# TLM_002_MAX6675.net
KiCad netlist of a schematic drawn in Altium Designer
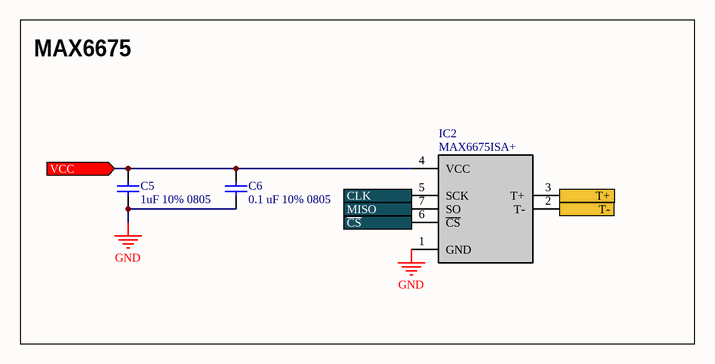
[diagram p0: TLM_002_MAX6675.SchDoc]

(export (version "E")
  (design (tool "Eeschema 10.0.6"))
  (components
    (comp (ref "C5")
      (value "1uF 10% 0805")
      (footprint "CAPC2013X145X50NL20T20")
      (fields (field (name "PART NUMBER") "VJ0805Y105KXQRW1BC") (field (name "MANUFACTURER") "Vitramon"))
      (libsource (lib "Altium Content Vault") (part "CAP"))
    )
    (comp (ref "C6")
      (value "0.1 uF 10% 0805")
      (footprint "CAPC2013X140X50ML20T25")
      (fields
        (field (name "PART NUMBER") "0805DD104KAT2A")
        (field (name "MANUFACTURER") "AVX Interconnect / Elco")
      )
      (libsource (lib "Altium Content Vault") (part "CAP"))
    )
    (comp (ref "IC2")
      (value "MAX6675ISA+")
      (footprint "SamacSys:SOIC127P600X175-8N")
      (description "Integrated Circuit")
      (fields (field (name "MOUSER PART NUMBER") "700-MAX6675ISA"))
      (libsource (lib "SamacSys") (part "MAX6675ISA+"))
    )
  )
  (nets
    (net (code "1") (name "/CLK") (class "Default")
      (node (ref "IC2") (pin "5") (pinfunction "SCK_5") (pintype "passive"))
    )
    (net (code "2") (name "/MISO") (class "Default")
      (node (ref "IC2") (pin "7") (pinfunction "SO_7") (pintype "passive"))
    )
    (net (code "3") (name "/T+") (class "Default")
      (node (ref "IC2") (pin "3") (pinfunction "T+_3") (pintype "passive"))
    )
    (net (code "4") (name "/T-") (class "Default")
      (node (ref "IC2") (pin "2") (pinfunction "T-_2") (pintype "passive"))
    )
    (net (code "5") (name "/VCC") (class "Default")
      (node (ref "C5") (pin "2") (pinfunction "2_2") (pintype "passive"))
      (node (ref "C6") (pin "2") (pinfunction "2_2") (pintype "passive"))
      (node (ref "IC2") (pin "4") (pinfunction "VCC_4") (pintype "passive"))
    )
    (net (code "6") (name "/~{CS}") (class "Default")
      (node (ref "IC2") (pin "6") (pinfunction "~{CS}_6") (pintype "passive"))
    )
    (net (code "7") (name "GND") (class "Default")
      (node (ref "C5") (pin "1") (pinfunction "1_1") (pintype "passive"))
      (node (ref "C6") (pin "1") (pinfunction "1_1") (pintype "passive"))
      (node (ref "IC2") (pin "1") (pinfunction "GND_1") (pintype "passive"))
    )
  )
)
